# abernode.net
KiCad netlist of a schematic drawn in EAGLE
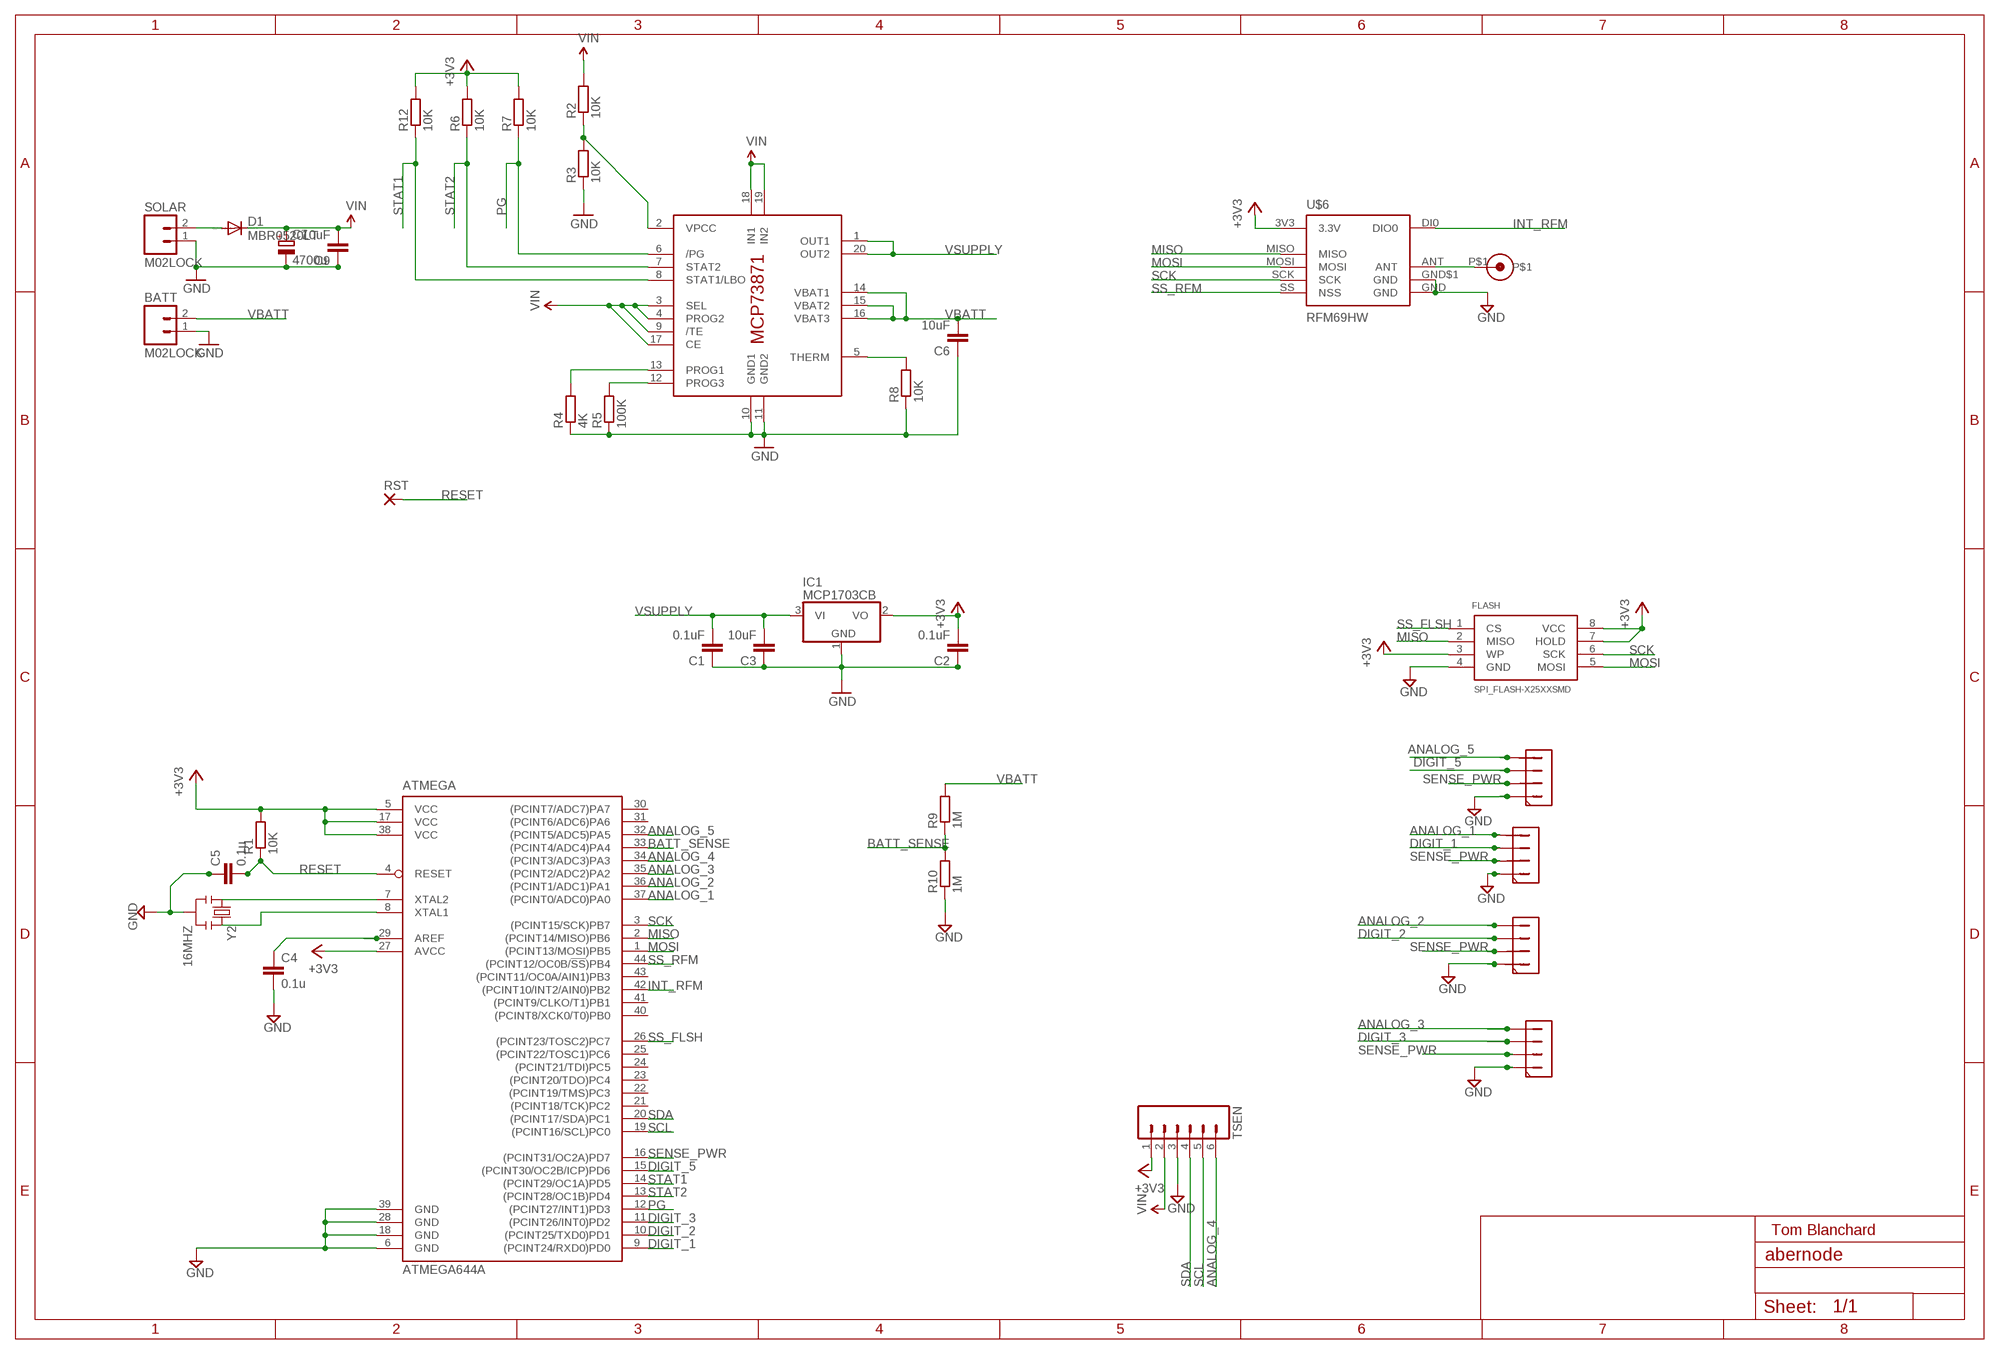
[diagram p0: schematic, sheet 1]

(export (version "E")
  (design (tool "Eeschema 10.0.6"))
  (components
    (comp (ref "ATMEGA")
      (value "ATMEGA644A")
      (footprint "eagle-import:TQFP44")
      (fields (field (name "MPN") "ATMEGA644PV-10AU"))
      (libsource (lib "eagle-import") (part "ATMEGA644A"))
    )
    (comp (ref "BATT")
      (value "M02LOCK")
      (footprint "eagle-import:1X02_LOCK")
      (libsource (lib "eagle-import") (part "M02LOCK"))
    )
    (comp (ref "C1")
      (value "0.1uF")
      (footprint "eagle-import:C0603")
      (libsource (lib "eagle-import") (part "C-EUC0603"))
    )
    (comp (ref "C2")
      (value "0.1uF")
      (footprint "eagle-import:C0603")
      (libsource (lib "eagle-import") (part "C-EUC0603"))
    )
    (comp (ref "C3")
      (value "10uF")
      (footprint "eagle-import:C0805")
      (libsource (lib "eagle-import") (part "C-EUC0805"))
    )
    (comp (ref "C4")
      (value "0.1u")
      (footprint "eagle-import:C0603")
      (libsource (lib "eagle-import") (part "C-EUC0603"))
    )
    (comp (ref "C5")
      (value "0.1u")
      (footprint "eagle-import:C0603")
      (libsource (lib "eagle-import") (part "C-EUC0603"))
    )
    (comp (ref "C6")
      (value "10uF")
      (footprint "eagle-import:C0805")
      (libsource (lib "eagle-import") (part "C-EUC0805"))
    )
    (comp (ref "C7")
      (value "4700u")
      (footprint "eagle-import:E7,5-18")
      (libsource (lib "eagle-import") (part "CPOL-EUE7.5-18"))
    )
    (comp (ref "C9")
      (value "10uF")
      (footprint "eagle-import:C0805")
      (libsource (lib "eagle-import") (part "C-EUC0805"))
    )
    (comp (ref "D1")
      (value "MBR0520LT")
      (footprint "eagle-import:SOD123")
      (libsource (lib "eagle-import") (part "MBR0520LT"))
    )
    (comp (ref "FLASH")
      (value "SPI_FLASH-X25XXSMD")
      (footprint "eagle-import:SO08")
      (libsource (lib "eagle-import") (part "SPI_FLASH-X25XXSMD"))
    )
    (comp (ref "IC1")
      (value "MCP1703CB")
      (footprint "eagle-import:SOT23")
      (libsource (lib "eagle-import") (part "MCP1703CB"))
    )
    (comp (ref "IC2")
      (value "MCP73871")
      (footprint "eagle-import:QFN20")
      (libsource (lib "eagle-import") (part "MCP73871"))
    )
    (comp (ref "R1")
      (value "10K")
      (footprint "eagle-import:R0603")
      (libsource (lib "eagle-import") (part "R-EU_R0603"))
    )
    (comp (ref "R2")
      (value "10K")
      (footprint "eagle-import:R0603")
      (libsource (lib "eagle-import") (part "R-EU_R0603"))
    )
    (comp (ref "R3")
      (value "10K")
      (footprint "eagle-import:R0603")
      (libsource (lib "eagle-import") (part "R-EU_R0603"))
    )
    (comp (ref "R4")
      (value "4K")
      (footprint "eagle-import:R0603")
      (libsource (lib "eagle-import") (part "R-EU_R0603"))
    )
    (comp (ref "R5")
      (value "100K")
      (footprint "eagle-import:R0603")
      (libsource (lib "eagle-import") (part "R-EU_R0603"))
    )
    (comp (ref "R6")
      (value "10K")
      (footprint "eagle-import:R0603")
      (libsource (lib "eagle-import") (part "R-EU_R0603"))
    )
    (comp (ref "R7")
      (value "10K")
      (footprint "eagle-import:R0603")
      (libsource (lib "eagle-import") (part "R-EU_R0603"))
    )
    (comp (ref "R8")
      (value "10K")
      (footprint "eagle-import:R0603")
      (libsource (lib "eagle-import") (part "R-EU_R0603"))
    )
    (comp (ref "R9")
      (value "1M")
      (footprint "eagle-import:R0603")
      (libsource (lib "eagle-import") (part "R-EU_R0603"))
    )
    (comp (ref "R10")
      (value "1M")
      (footprint "eagle-import:R0603")
      (libsource (lib "eagle-import") (part "R-EU_R0603"))
    )
    (comp (ref "R12")
      (value "10K")
      (footprint "eagle-import:R0603")
      (libsource (lib "eagle-import") (part "R-EU_R0603"))
    )
    (comp (ref "RST")
      (value "SMD2")
      (footprint "eagle-import:SMD1,27-2,54")
      (libsource (lib "eagle-import") (part "SMD2"))
    )
    (comp (ref "SEN1")
      (value "HEADER_4")
      (footprint "eagle-import:HEADER_4")
      (libsource (lib "eagle-import") (part "HEADER_4"))
    )
    (comp (ref "SEN2")
      (value "HEADER_4")
      (footprint "eagle-import:HEADER_4")
      (libsource (lib "eagle-import") (part "HEADER_4"))
    )
    (comp (ref "SEN3")
      (value "HEADER_4")
      (footprint "eagle-import:HEADER_4")
      (libsource (lib "eagle-import") (part "HEADER_4"))
    )
    (comp (ref "SEN4")
      (value "HEADER_4")
      (footprint "eagle-import:HEADER_4")
      (libsource (lib "eagle-import") (part "HEADER_4"))
    )
    (comp (ref "SOLAR")
      (value "M02LOCK")
      (footprint "eagle-import:1X02_LOCK")
      (libsource (lib "eagle-import") (part "M02LOCK"))
    )
    (comp (ref "TSEN")
      (value "M06LONGPADS")
      (footprint "eagle-import:1X06_LONGPADS")
      (libsource (lib "eagle-import") (part "M06LONGPADS"))
    )
    (comp (ref "U$6")
      (value "RFM69HW")
      (footprint "eagle-import:RFM69W-XXXS2")
      (libsource (lib "eagle-import") (part "RFM69HW"))
    )
    (comp (ref "U$7")
      (value "ANT")
      (footprint "eagle-import:ANT")
      (libsource (lib "eagle-import") (part "ANT"))
    )
    (comp (ref "Y2")
      (value "16MHZ")
      (footprint "eagle-import:RESONATOR-SMD")
      (libsource (lib "eagle-import") (part "RESONATOR16MHZ"))
    )
  )
  (nets
    (net (code "1") (name "+3V3") (class "Default")
      (node (ref "ATMEGA") (pin "17") (pinfunction "VCC_17") (pintype "power_in"))
      (node (ref "ATMEGA") (pin "27") (pinfunction "AVCC_27") (pintype "power_in"))
      (node (ref "ATMEGA") (pin "38") (pinfunction "VCC_38") (pintype "power_in"))
      (node (ref "ATMEGA") (pin "5") (pinfunction "VCC_5") (pintype "power_in"))
      (node (ref "C2") (pin "2") (pinfunction "2_2") (pintype "passive"))
      (node (ref "FLASH") (pin "3") (pinfunction "WP_3") (pintype "bidirectional"))
      (node (ref "FLASH") (pin "7") (pinfunction "HOLD_7") (pintype "bidirectional"))
      (node (ref "FLASH") (pin "8") (pinfunction "VCC_8") (pintype "bidirectional"))
      (node (ref "IC1") (pin "2") (pinfunction "VO_2") (pintype "passive"))
      (node (ref "R1") (pin "2") (pinfunction "2_2") (pintype "passive"))
      (node (ref "R12") (pin "2") (pinfunction "2_2") (pintype "passive"))
      (node (ref "R6") (pin "2") (pinfunction "2_2") (pintype "passive"))
      (node (ref "R7") (pin "2") (pinfunction "2_2") (pintype "passive"))
      (node (ref "TSEN") (pin "1") (pinfunction "1_1") (pintype "passive"))
      (node (ref "U$6") (pin "3V3") (pinfunction "3.3V_3V3") (pintype "power_in"))
    )
    (net (code "2") (name "/ANALOG_1") (class "Default")
      (node (ref "ATMEGA") (pin "37") (pinfunction "(PCINT0/ADC0)PA0_37") (pintype "bidirectional"))
      (node (ref "SEN2") (pin "4") (pinfunction "P$4_4") (pintype "bidirectional"))
    )
    (net (code "3") (name "/ANALOG_2") (class "Default")
      (node (ref "ATMEGA") (pin "36") (pinfunction "(PCINT1/ADC1)PA1_36") (pintype "bidirectional"))
      (node (ref "SEN1") (pin "4") (pinfunction "P$4_4") (pintype "bidirectional"))
    )
    (net (code "4") (name "/ANALOG_3") (class "Default")
      (node (ref "ATMEGA") (pin "35") (pinfunction "(PCINT2/ADC2)PA2_35") (pintype "bidirectional"))
      (node (ref "SEN4") (pin "4") (pinfunction "P$4_4") (pintype "bidirectional"))
    )
    (net (code "5") (name "/ANALOG_4") (class "Default")
      (node (ref "ATMEGA") (pin "34") (pinfunction "(PCINT3/ADC3)PA3_34") (pintype "bidirectional"))
      (node (ref "TSEN") (pin "6") (pinfunction "6_6") (pintype "passive"))
    )
    (net (code "6") (name "/ANALOG_5") (class "Default")
      (node (ref "ATMEGA") (pin "32") (pinfunction "(PCINT5/ADC5)PA5_32") (pintype "bidirectional"))
      (node (ref "SEN3") (pin "4") (pinfunction "P$4_4") (pintype "bidirectional"))
    )
    (net (code "7") (name "/BATT_SENSE") (class "Default")
      (node (ref "ATMEGA") (pin "33") (pinfunction "(PCINT4/ADC4)PA4_33") (pintype "bidirectional"))
      (node (ref "R10") (pin "2") (pinfunction "2_2") (pintype "passive"))
      (node (ref "R9") (pin "1") (pinfunction "1_1") (pintype "passive"))
    )
    (net (code "8") (name "/DIGIT_1") (class "Default")
      (node (ref "ATMEGA") (pin "9") (pinfunction "(PCINT24/RXD0)PD0_9") (pintype "bidirectional"))
      (node (ref "SEN2") (pin "3") (pinfunction "P$3_3") (pintype "bidirectional"))
    )
    (net (code "9") (name "/DIGIT_2") (class "Default")
      (node (ref "ATMEGA") (pin "10") (pinfunction "(PCINT25/TXD0)PD1_10") (pintype "bidirectional"))
      (node (ref "SEN1") (pin "3") (pinfunction "P$3_3") (pintype "bidirectional"))
    )
    (net (code "10") (name "/DIGIT_3") (class "Default")
      (node (ref "ATMEGA") (pin "11") (pinfunction "(PCINT26/INT0)PD2_11") (pintype "bidirectional"))
      (node (ref "SEN4") (pin "3") (pinfunction "P$3_3") (pintype "bidirectional"))
    )
    (net (code "11") (name "/DIGIT_5") (class "Default")
      (node (ref "ATMEGA") (pin "15") (pinfunction "(PCINT30/OC2B/ICP)PD6_15") (pintype "bidirectional"))
      (node (ref "SEN3") (pin "3") (pinfunction "P$3_3") (pintype "bidirectional"))
    )
    (net (code "12") (name "/INT_RFM") (class "Default")
      (node (ref "ATMEGA") (pin "42") (pinfunction "(PCINT10/INT2/AIN0)PB2_42") (pintype "bidirectional"))
      (node (ref "U$6") (pin "DI0") (pinfunction "DIO0_DI0") (pintype "bidirectional"))
    )
    (net (code "13") (name "/MISO") (class "Default")
      (node (ref "ATMEGA") (pin "2") (pinfunction "(PCINT14/MISO)PB6_2") (pintype "bidirectional"))
      (node (ref "FLASH") (pin "2") (pinfunction "MISO_2") (pintype "bidirectional"))
      (node (ref "U$6") (pin "MISO") (pinfunction "MISO_MISO") (pintype "bidirectional"))
    )
    (net (code "14") (name "/MOSI") (class "Default")
      (node (ref "ATMEGA") (pin "1") (pinfunction "(PCINT13/MOSI)PB5_1") (pintype "bidirectional"))
      (node (ref "FLASH") (pin "5") (pinfunction "MOSI_5") (pintype "bidirectional"))
      (node (ref "U$6") (pin "MOSI") (pinfunction "MOSI_MOSI") (pintype "input"))
    )
    (net (code "15") (name "/PG") (class "Default")
      (node (ref "ATMEGA") (pin "12") (pinfunction "(PCINT27/INT1)PD3_12") (pintype "bidirectional"))
      (node (ref "IC2") (pin "6") (pinfunction "/PG_6") (pintype "output"))
      (node (ref "R7") (pin "1") (pinfunction "1_1") (pintype "passive"))
    )
    (net (code "16") (name "/RESET") (class "Default")
      (node (ref "ATMEGA") (pin "4") (pinfunction "RESET_4") (pintype "input"))
      (node (ref "C5") (pin "2") (pinfunction "2_2") (pintype "passive"))
      (node (ref "R1") (pin "1") (pinfunction "1_1") (pintype "passive"))
      (node (ref "RST") (pin "1") (pinfunction "P_1") (pintype "passive"))
    )
    (net (code "17") (name "/SCK") (class "Default")
      (node (ref "ATMEGA") (pin "3") (pinfunction "(PCINT15/SCK)PB7_3") (pintype "bidirectional"))
      (node (ref "FLASH") (pin "6") (pinfunction "SCK_6") (pintype "bidirectional"))
      (node (ref "U$6") (pin "SCK") (pinfunction "SCK_SCK") (pintype "input"))
    )
    (net (code "18") (name "/SCL") (class "Default")
      (node (ref "ATMEGA") (pin "19") (pinfunction "(PCINT16/SCL)PC0_19") (pintype "output"))
      (node (ref "TSEN") (pin "5") (pinfunction "5_5") (pintype "passive"))
    )
    (net (code "19") (name "/SDA") (class "Default")
      (node (ref "ATMEGA") (pin "20") (pinfunction "(PCINT17/SDA)PC1_20") (pintype "output"))
      (node (ref "TSEN") (pin "4") (pinfunction "4_4") (pintype "passive"))
    )
    (net (code "20") (name "/SENSE_PWR") (class "Default")
      (node (ref "ATMEGA") (pin "16") (pinfunction "(PCINT31/OC2A)PD7_16") (pintype "bidirectional"))
      (node (ref "SEN1") (pin "2") (pinfunction "P$2_2") (pintype "bidirectional"))
      (node (ref "SEN2") (pin "2") (pinfunction "P$2_2") (pintype "bidirectional"))
      (node (ref "SEN3") (pin "2") (pinfunction "P$2_2") (pintype "bidirectional"))
      (node (ref "SEN4") (pin "2") (pinfunction "P$2_2") (pintype "bidirectional"))
    )
    (net (code "21") (name "/SS_FLSH") (class "Default")
      (node (ref "ATMEGA") (pin "26") (pinfunction "(PCINT23/TOSC2)PC7_26") (pintype "output"))
      (node (ref "FLASH") (pin "1") (pinfunction "CS_1") (pintype "bidirectional"))
    )
    (net (code "22") (name "/SS_RFM") (class "Default")
      (node (ref "ATMEGA") (pin "44") (pinfunction "(PCINT12/OC0B/~{SS})PB4_44") (pintype "bidirectional"))
      (node (ref "U$6") (pin "SS") (pinfunction "NSS_SS") (pintype "input"))
    )
    (net (code "23") (name "/STAT1") (class "Default")
      (node (ref "ATMEGA") (pin "14") (pinfunction "(PCINT29/OC1A)PD5_14") (pintype "bidirectional"))
      (node (ref "IC2") (pin "8") (pinfunction "STAT1/LBO_8") (pintype "output"))
      (node (ref "R12") (pin "1") (pinfunction "1_1") (pintype "passive"))
    )
    (net (code "24") (name "/STAT2") (class "Default")
      (node (ref "ATMEGA") (pin "13") (pinfunction "(PCINT28/OC1B)PD4_13") (pintype "bidirectional"))
      (node (ref "IC2") (pin "7") (pinfunction "STAT2_7") (pintype "output"))
      (node (ref "R6") (pin "1") (pinfunction "1_1") (pintype "passive"))
    )
    (net (code "25") (name "/VBATT") (class "Default")
      (node (ref "BATT") (pin "2") (pinfunction "2_2") (pintype "passive"))
      (node (ref "C6") (pin "2") (pinfunction "2_2") (pintype "passive"))
      (node (ref "IC2") (pin "14") (pinfunction "VBAT1_14") (pintype "output"))
      (node (ref "IC2") (pin "15") (pinfunction "VBAT2_15") (pintype "output"))
      (node (ref "IC2") (pin "16") (pinfunction "VBAT3_16") (pintype "output"))
      (node (ref "R9") (pin "2") (pinfunction "2_2") (pintype "passive"))
    )
    (net (code "26") (name "/VSUPPLY") (class "Default")
      (node (ref "C1") (pin "2") (pinfunction "2_2") (pintype "passive"))
      (node (ref "C3") (pin "2") (pinfunction "2_2") (pintype "passive"))
      (node (ref "IC1") (pin "3") (pinfunction "VI_3") (pintype "input"))
      (node (ref "IC2") (pin "1") (pinfunction "OUT1_1") (pintype "output"))
      (node (ref "IC2") (pin "20") (pinfunction "OUT2_20") (pintype "output"))
    )
    (net (code "27") (name "GND") (class "Default")
      (node (ref "ATMEGA") (pin "18") (pinfunction "GND_18") (pintype "power_in"))
      (node (ref "ATMEGA") (pin "28") (pinfunction "GND_28") (pintype "power_in"))
      (node (ref "ATMEGA") (pin "39") (pinfunction "GND_39") (pintype "power_in"))
      (node (ref "ATMEGA") (pin "6") (pinfunction "GND_6") (pintype "power_in"))
      (node (ref "BATT") (pin "1") (pinfunction "1_1") (pintype "passive"))
      (node (ref "C1") (pin "1") (pinfunction "1_1") (pintype "passive"))
      (node (ref "C2") (pin "1") (pinfunction "1_1") (pintype "passive"))
      (node (ref "C3") (pin "1") (pinfunction "1_1") (pintype "passive"))
      (node (ref "C4") (pin "2") (pinfunction "2_2") (pintype "passive"))
      (node (ref "C5") (pin "1") (pinfunction "1_1") (pintype "passive"))
      (node (ref "C6") (pin "1") (pinfunction "1_1") (pintype "passive"))
      (node (ref "C7") (pin "-") (pinfunction "-_-") (pintype "passive"))
      (node (ref "C9") (pin "1") (pinfunction "1_1") (pintype "passive"))
      (node (ref "FLASH") (pin "4") (pinfunction "GND_4") (pintype "bidirectional"))
      (node (ref "IC1") (pin "1") (pinfunction "GND_1") (pintype "passive"))
      (node (ref "IC2") (pin "10") (pinfunction "GND1_10") (pintype "power_in"))
      (node (ref "IC2") (pin "11") (pinfunction "GND2_11") (pintype "power_in"))
      (node (ref "R10") (pin "1") (pinfunction "1_1") (pintype "passive"))
      (node (ref "R3") (pin "1") (pinfunction "1_1") (pintype "passive"))
      (node (ref "R4") (pin "1") (pinfunction "1_1") (pintype "passive"))
      (node (ref "R5") (pin "1") (pinfunction "1_1") (pintype "passive"))
      (node (ref "R8") (pin "1") (pinfunction "1_1") (pintype "passive"))
      (node (ref "SEN1") (pin "1") (pinfunction "P$1_1") (pintype "bidirectional"))
      (node (ref "SEN2") (pin "1") (pinfunction "P$1_1") (pintype "bidirectional"))
      (node (ref "SEN3") (pin "1") (pinfunction "P$1_1") (pintype "bidirectional"))
      (node (ref "SEN4") (pin "1") (pinfunction "P$1_1") (pintype "bidirectional"))
      (node (ref "SOLAR") (pin "1") (pinfunction "1_1") (pintype "passive"))
      (node (ref "TSEN") (pin "3") (pinfunction "3_3") (pintype "passive"))
      (node (ref "U$6") (pin "GND") (pinfunction "GND_GND") (pintype "power_in"))
      (node (ref "U$6") (pin "GND$1") (pinfunction "GND_GND$1") (pintype "power_in"))
      (node (ref "Y2") (pin "2") (pinfunction "2_2") (pintype "passive"))
    )
    (net (code "28") (name "Net-(ATMEGA-AREF)") (class "Default")
      (node (ref "ATMEGA") (pin "29") (pinfunction "AREF_29") (pintype "passive"))
      (node (ref "C4") (pin "1") (pinfunction "1_1") (pintype "passive"))
    )
    (net (code "29") (name "Net-(ATMEGA-XTAL1)") (class "Default")
      (node (ref "ATMEGA") (pin "8") (pinfunction "XTAL1_8") (pintype "bidirectional"))
      (node (ref "Y2") (pin "3") (pinfunction "3_3") (pintype "passive"))
    )
    (net (code "30") (name "Net-(ATMEGA-XTAL2)") (class "Default")
      (node (ref "ATMEGA") (pin "7") (pinfunction "XTAL2_7") (pintype "bidirectional"))
      (node (ref "Y2") (pin "1") (pinfunction "1_1") (pintype "passive"))
    )
    (net (code "31") (name "Net-(D1-PadA)") (class "Default")
      (node (ref "D1") (pin "A") (pinfunction "A_A") (pintype "passive"))
      (node (ref "SOLAR") (pin "2") (pinfunction "2_2") (pintype "passive"))
    )
    (net (code "32") (name "Net-(IC2-PROG1)") (class "Default")
      (node (ref "IC2") (pin "13") (pinfunction "PROG1_13") (pintype "input"))
      (node (ref "R4") (pin "2") (pinfunction "2_2") (pintype "passive"))
    )
    (net (code "33") (name "Net-(IC2-PROG3)") (class "Default")
      (node (ref "IC2") (pin "12") (pinfunction "PROG3_12") (pintype "input"))
      (node (ref "R5") (pin "2") (pinfunction "2_2") (pintype "passive"))
    )
    (net (code "34") (name "Net-(IC2-THERM)") (class "Default")
      (node (ref "IC2") (pin "5") (pinfunction "THERM_5") (pintype "input"))
      (node (ref "R8") (pin "2") (pinfunction "2_2") (pintype "passive"))
    )
    (net (code "35") (name "Net-(IC2-VPCC)") (class "Default")
      (node (ref "IC2") (pin "2") (pinfunction "VPCC_2") (pintype "input"))
      (node (ref "R2") (pin "1") (pinfunction "1_1") (pintype "passive"))
      (node (ref "R3") (pin "2") (pinfunction "2_2") (pintype "passive"))
    )
    (net (code "36") (name "Net-(U$6-PadANT)") (class "Default")
      (node (ref "U$6") (pin "ANT") (pinfunction "ANT_ANT") (pintype "passive"))
      (node (ref "U$7") (pin "P$1") (pinfunction "P$1_P$1") (pintype "bidirectional"))
    )
    (net (code "37") (name "VIN") (class "Default")
      (node (ref "C7") (pin "+") (pinfunction "+_+") (pintype "passive"))
      (node (ref "C9") (pin "2") (pinfunction "2_2") (pintype "passive"))
      (node (ref "D1") (pin "C") (pinfunction "C_C") (pintype "passive"))
      (node (ref "IC2") (pin "17") (pinfunction "CE_17") (pintype "input"))
      (node (ref "IC2") (pin "18") (pinfunction "IN1_18") (pintype "input"))
      (node (ref "IC2") (pin "19") (pinfunction "IN2_19") (pintype "input"))
      (node (ref "IC2") (pin "3") (pinfunction "SEL_3") (pintype "input"))
      (node (ref "IC2") (pin "4") (pinfunction "PROG2_4") (pintype "input"))
      (node (ref "IC2") (pin "9") (pinfunction "/TE_9") (pintype "input"))
      (node (ref "R2") (pin "2") (pinfunction "2_2") (pintype "passive"))
      (node (ref "TSEN") (pin "2") (pinfunction "2_2") (pintype "passive"))
    )
    (net (code "38") (name "unconnected-(ATMEGA-(PCINT6{slash}ADC6)PA6-Pad31)") (class "Default")
      (node (ref "ATMEGA") (pin "31") (pinfunction "(PCINT6/ADC6)PA6_31") (pintype "bidirectional"))
    )
    (net (code "39") (name "unconnected-(ATMEGA-(PCINT7{slash}ADC7)PA7-Pad30)") (class "Default")
      (node (ref "ATMEGA") (pin "30") (pinfunction "(PCINT7/ADC7)PA7_30") (pintype "bidirectional"))
    )
    (net (code "40") (name "unconnected-(ATMEGA-(PCINT8{slash}XCK0{slash}T0)PB0-Pad40)") (class "Default")
      (node (ref "ATMEGA") (pin "40") (pinfunction "(PCINT8/XCK0/T0)PB0_40") (pintype "bidirectional"))
    )
    (net (code "41") (name "unconnected-(ATMEGA-(PCINT9{slash}CLKO{slash}T1)PB1-Pad41)") (class "Default")
      (node (ref "ATMEGA") (pin "41") (pinfunction "(PCINT9/CLKO/T1)PB1_41") (pintype "bidirectional"))
    )
    (net (code "42") (name "unconnected-(ATMEGA-(PCINT11{slash}OC0A{slash}AIN1)PB3-Pad43)") (class "Default")
      (node (ref "ATMEGA") (pin "43") (pinfunction "(PCINT11/OC0A/AIN1)PB3_43") (pintype "bidirectional"))
    )
    (net (code "43") (name "unconnected-(ATMEGA-(PCINT18{slash}TCK)PC2-Pad21)") (class "Default")
      (node (ref "ATMEGA") (pin "21") (pinfunction "(PCINT18/TCK)PC2_21") (pintype "output"))
    )
    (net (code "44") (name "unconnected-(ATMEGA-(PCINT19{slash}TMS)PC3-Pad22)") (class "Default")
      (node (ref "ATMEGA") (pin "22") (pinfunction "(PCINT19/TMS)PC3_22") (pintype "output"))
    )
    (net (code "45") (name "unconnected-(ATMEGA-(PCINT20{slash}TDO)PC4-Pad23)") (class "Default")
      (node (ref "ATMEGA") (pin "23") (pinfunction "(PCINT20/TDO)PC4_23") (pintype "output"))
    )
    (net (code "46") (name "unconnected-(ATMEGA-(PCINT21{slash}TDI)PC5-Pad24)") (class "Default")
      (node (ref "ATMEGA") (pin "24") (pinfunction "(PCINT21/TDI)PC5_24") (pintype "output"))
    )
    (net (code "47") (name "unconnected-(ATMEGA-(PCINT22{slash}TOSC1)PC6-Pad25)") (class "Default")
      (node (ref "ATMEGA") (pin "25") (pinfunction "(PCINT22/TOSC1)PC6_25") (pintype "output"))
    )
  )
)
